# STM32F103C8T6.net
KiCad netlist of a schematic drawn in Altium Designer
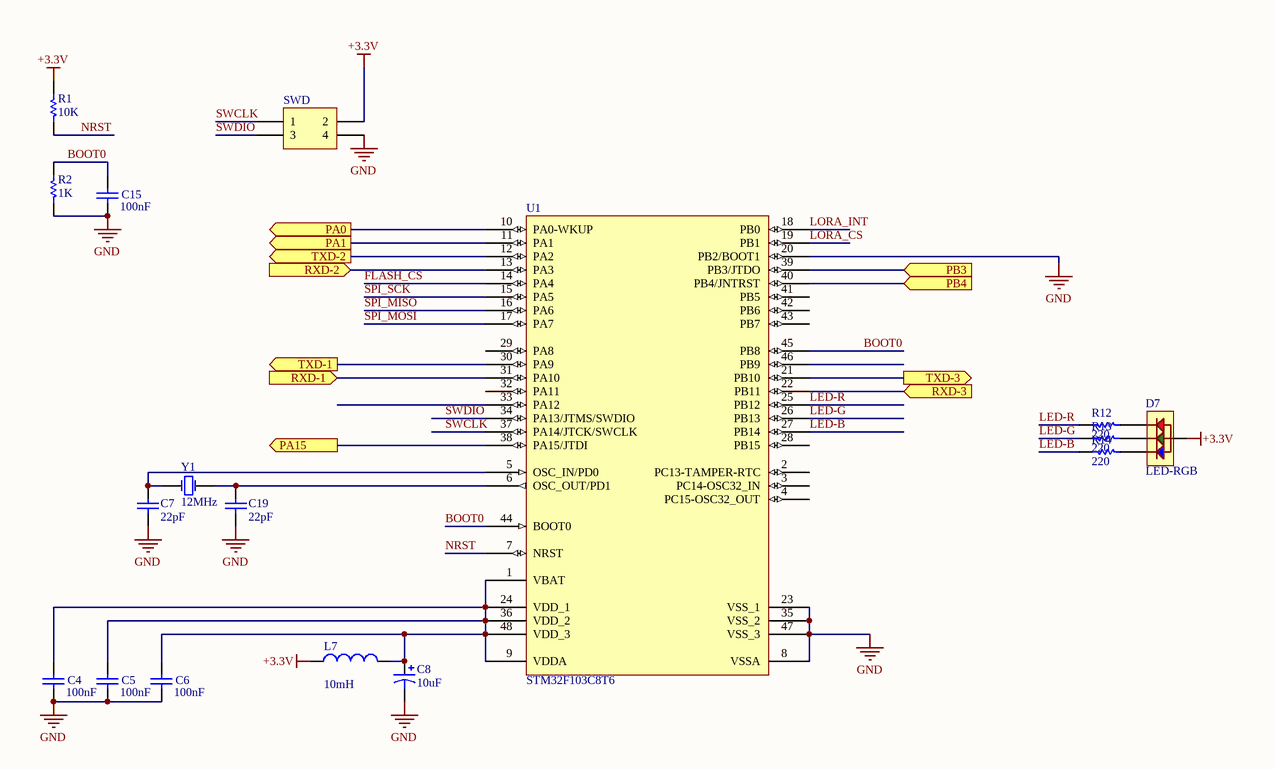
[diagram p0: STM32F103C8T6.SchDoc]

(export (version "E")
  (design (tool "Eeschema 10.0.6"))
  (components
    (comp (ref "C4")
      (value "100nF")
      (footprint "C603")
      (description "Capacitor")
      (fields (field (name "DESIGNER") "Parsa Malekpour"))
      (libsource (lib "UserPKG") (part "Cap"))
    )
    (comp (ref "C5")
      (value "100nF")
      (footprint "C603")
      (description "Capacitor")
      (fields (field (name "DESIGNER") "Parsa Malekpour"))
      (libsource (lib "UserPKG") (part "Cap"))
    )
    (comp (ref "C6")
      (value "100nF")
      (footprint "C603")
      (description "Capacitor")
      (fields (field (name "DESIGNER") "Parsa Malekpour"))
      (libsource (lib "UserPKG") (part "Cap"))
    )
    (comp (ref "C7")
      (value "22pF")
      (footprint "C603")
      (description "Capacitor")
      (fields (field (name "DESIGNER") "Parsa Malekpour"))
      (libsource (lib "UserPKG") (part "Cap"))
    )
    (comp (ref "C8")
      (value "10uF")
      (footprint "c805")
      (description "Polar Capacitor")
      (fields (field (name "VOLTAGE") "10V"))
      (libsource (lib "UserPKG") (part "CAP-POL"))
    )
    (comp (ref "C15")
      (value "100nF")
      (footprint "C603")
      (description "Capacitor")
      (fields (field (name "DESIGNER") "Parsa Malekpour"))
      (libsource (lib "UserPKG") (part "Cap"))
    )
    (comp (ref "C19")
      (value "22pF")
      (footprint "C603")
      (description "Capacitor")
      (fields (field (name "DESIGNER") "Parsa Malekpour"))
      (libsource (lib "UserPKG") (part "Cap"))
    )
    (comp (ref "D7")
      (value "LED-RGB")
      (footprint "LED-1210")
      (libsource (lib "ParsaLibrary") (part "LED-RGB-1210"))
    )
    (comp (ref "L7")
      (value "10mH")
      (footprint "R805")
      (description "Inductor")
      (fields (field (name "PUBLISHER") "Altium Limited"))
      (libsource (lib "Miscellaneous Devices") (part "Inductor"))
    )
    (comp (ref "R1")
      (value "10K")
      (footprint "R0603")
      (description "Resistor")
      (fields (field (name "DESIGNER") "Parsa Malekpour"))
      (libsource (lib "UserPKG") (part "Resistor"))
    )
    (comp (ref "R2")
      (value "1K")
      (footprint "R0603")
      (description "Resistor")
      (fields (field (name "DESIGNER") "Parsa Malekpour"))
      (libsource (lib "UserPKG") (part "Resistor"))
    )
    (comp (ref "R12")
      (value "220")
      (footprint "R0603")
      (description "Resistor")
      (fields (field (name "DESIGNER") "Parsa Malekpour"))
      (libsource (lib "UserPKG") (part "Resistor"))
    )
    (comp (ref "R13")
      (value "220")
      (footprint "R0603")
      (description "Resistor")
      (fields (field (name "DESIGNER") "Parsa Malekpour"))
      (libsource (lib "UserPKG") (part "Resistor"))
    )
    (comp (ref "R14")
      (value "220")
      (footprint "R0603")
      (description "Resistor")
      (fields (field (name "DESIGNER") "Parsa Malekpour"))
      (libsource (lib "UserPKG") (part "Resistor"))
    )
    (comp (ref "SWD")
      (value "MHDR2X2")
      (footprint "PHDR-2MM-2X2")
      (description "Header, 2-Pin, Dual row")
      (fields (field (name "PUBLISHER") "Altium Limited"))
      (libsource (lib "Miscellaneous Connectors") (part "MHDR2X2"))
    )
    (comp (ref "U1")
      (value "STM32F103C8T6")
      (footprint "LQFP-48")
      (description "STM32 ARM-based 32-bit MCU with 64 Kbytes Flash, 48-pin LQFP, Industrial Temperature")
      (fields (field (name "PUBLISHER") "Altium Limited"))
      (libsource (lib "ST Microcontroller 32-Bit STM32") (part "STM32F103C8T6"))
    )
    (comp (ref "Y1")
      (value "12MHz")
      (footprint "XTAL-SMD")
      (description "Crystal Oscillator")
      (fields (field (name "DESIGNER") "Parsa Malekpour") (field (name "EMAIL") "Malekpour.parsa@Gmail.com"))
      (libsource (lib "ParsaLibrary") (part "XTAL"))
    )
  )
  (nets
    (net (code "1") (name "+3.3V") (class "Default")
      (node (ref "D7") (pin "4") (pinfunction "COM_4") (pintype "passive"))
      (node (ref "L7") (pin "1") (pinfunction "1_1") (pintype "passive"))
      (node (ref "R1") (pin "2") (pinfunction "2_2") (pintype "passive"))
      (node (ref "SWD") (pin "2") (pinfunction "2_2") (pintype "passive"))
    )
    (net (code "2") (name "/BOOT0") (class "Default")
      (node (ref "C15") (pin "2") (pinfunction "2_2") (pintype "passive"))
      (node (ref "R2") (pin "2") (pinfunction "2_2") (pintype "passive"))
      (node (ref "U1") (pin "44") (pinfunction "BOOT0_44") (pintype "input"))
      (node (ref "U1") (pin "45") (pinfunction "PB8_45") (pintype "bidirectional"))
    )
    (net (code "3") (name "/FLASH_CS") (class "Default")
      (node (ref "U1") (pin "14") (pinfunction "PA4_14") (pintype "bidirectional"))
    )
    (net (code "4") (name "/LED-B") (class "Default")
      (node (ref "R14") (pin "2") (pinfunction "2_2") (pintype "passive"))
      (node (ref "U1") (pin "27") (pinfunction "PB14_27") (pintype "bidirectional"))
    )
    (net (code "5") (name "/LED-G") (class "Default")
      (node (ref "R13") (pin "2") (pinfunction "2_2") (pintype "passive"))
      (node (ref "U1") (pin "26") (pinfunction "PB13_26") (pintype "bidirectional"))
    )
    (net (code "6") (name "/LED-R") (class "Default")
      (node (ref "R12") (pin "2") (pinfunction "2_2") (pintype "passive"))
      (node (ref "U1") (pin "25") (pinfunction "PB12_25") (pintype "bidirectional"))
    )
    (net (code "7") (name "/LORA_CS") (class "Default")
      (node (ref "U1") (pin "19") (pinfunction "PB1_19") (pintype "bidirectional"))
    )
    (net (code "8") (name "/LORA_INT") (class "Default")
      (node (ref "U1") (pin "18") (pinfunction "PB0_18") (pintype "bidirectional"))
    )
    (net (code "9") (name "/NRST") (class "Default")
      (node (ref "R1") (pin "1") (pinfunction "1_1") (pintype "passive"))
      (node (ref "U1") (pin "7") (pinfunction "NRST_7") (pintype "bidirectional"))
    )
    (net (code "10") (name "/PA0") (class "Default")
      (node (ref "U1") (pin "10") (pinfunction "PA0-WKUP_10") (pintype "bidirectional"))
    )
    (net (code "11") (name "/PA1") (class "Default")
      (node (ref "U1") (pin "11") (pinfunction "PA1_11") (pintype "bidirectional"))
    )
    (net (code "12") (name "/PA15") (class "Default")
      (node (ref "U1") (pin "38") (pinfunction "PA15/JTDI_38") (pintype "bidirectional"))
    )
    (net (code "13") (name "/PB3") (class "Default")
      (node (ref "U1") (pin "39") (pinfunction "PB3/JTDO_39") (pintype "bidirectional"))
    )
    (net (code "14") (name "/PB4") (class "Default")
      (node (ref "U1") (pin "40") (pinfunction "PB4/JNTRST_40") (pintype "bidirectional"))
    )
    (net (code "15") (name "/RXD-1") (class "Default")
      (node (ref "U1") (pin "31") (pinfunction "PA10_31") (pintype "bidirectional"))
    )
    (net (code "16") (name "/RXD-2") (class "Default")
      (node (ref "U1") (pin "13") (pinfunction "PA3_13") (pintype "bidirectional"))
    )
    (net (code "17") (name "/RXD-3") (class "Default")
      (node (ref "U1") (pin "22") (pinfunction "PB11_22") (pintype "bidirectional"))
    )
    (net (code "18") (name "/SPI_MISO") (class "Default")
      (node (ref "U1") (pin "16") (pinfunction "PA6_16") (pintype "bidirectional"))
    )
    (net (code "19") (name "/SPI_MOSI") (class "Default")
      (node (ref "U1") (pin "17") (pinfunction "PA7_17") (pintype "bidirectional"))
    )
    (net (code "20") (name "/SPI_SCK") (class "Default")
      (node (ref "U1") (pin "15") (pinfunction "PA5_15") (pintype "bidirectional"))
    )
    (net (code "21") (name "/SWCLK") (class "Default")
      (node (ref "SWD") (pin "1") (pinfunction "1_1") (pintype "passive"))
      (node (ref "U1") (pin "37") (pinfunction "PA14/JTCK/SWCLK_37") (pintype "bidirectional"))
    )
    (net (code "22") (name "/SWDIO") (class "Default")
      (node (ref "SWD") (pin "3") (pinfunction "3_3") (pintype "passive"))
      (node (ref "U1") (pin "34") (pinfunction "PA13/JTMS/SWDIO_34") (pintype "bidirectional"))
    )
    (net (code "23") (name "/TXD-1") (class "Default")
      (node (ref "U1") (pin "30") (pinfunction "PA9_30") (pintype "bidirectional"))
    )
    (net (code "24") (name "/TXD-2") (class "Default")
      (node (ref "U1") (pin "12") (pinfunction "PA2_12") (pintype "bidirectional"))
    )
    (net (code "25") (name "/TXD-3") (class "Default")
      (node (ref "U1") (pin "21") (pinfunction "PB10_21") (pintype "bidirectional"))
    )
    (net (code "26") (name "GND") (class "Default")
      (node (ref "C15") (pin "1") (pinfunction "1_1") (pintype "passive"))
      (node (ref "C19") (pin "2") (pinfunction "2_2") (pintype "passive"))
      (node (ref "C4") (pin "1") (pinfunction "1_1") (pintype "passive"))
      (node (ref "C5") (pin "1") (pinfunction "1_1") (pintype "passive"))
      (node (ref "C6") (pin "1") (pinfunction "1_1") (pintype "passive"))
      (node (ref "C7") (pin "2") (pinfunction "2_2") (pintype "passive"))
      (node (ref "C8") (pin "2") (pinfunction "2_2") (pintype "passive"))
      (node (ref "R2") (pin "1") (pinfunction "1_1") (pintype "passive"))
      (node (ref "SWD") (pin "4") (pinfunction "4_4") (pintype "passive"))
      (node (ref "U1") (pin "20") (pinfunction "PB2/BOOT1_20") (pintype "bidirectional"))
      (node (ref "U1") (pin "23") (pinfunction "VSS_1_23") (pintype "power_in"))
      (node (ref "U1") (pin "35") (pinfunction "VSS_2_35") (pintype "power_in"))
      (node (ref "U1") (pin "47") (pinfunction "VSS_3_47") (pintype "power_in"))
      (node (ref "U1") (pin "8") (pinfunction "VSSA_8") (pintype "power_in"))
    )
    (net (code "27") (name "Net-(D7-B)") (class "Default")
      (node (ref "D7") (pin "1") (pinfunction "B_1") (pintype "passive"))
      (node (ref "R14") (pin "1") (pinfunction "1_1") (pintype "passive"))
    )
    (net (code "28") (name "Net-(D7-G)") (class "Default")
      (node (ref "D7") (pin "2") (pinfunction "G_2") (pintype "passive"))
      (node (ref "R13") (pin "1") (pinfunction "1_1") (pintype "passive"))
    )
    (net (code "29") (name "Net-(D7-R)") (class "Default")
      (node (ref "D7") (pin "3") (pinfunction "R_3") (pintype "passive"))
      (node (ref "R12") (pin "1") (pinfunction "1_1") (pintype "passive"))
    )
    (net (code "30") (name "Net-(U1-OSC_IN{slash}PD0)") (class "Default")
      (node (ref "C7") (pin "1") (pinfunction "1_1") (pintype "passive"))
      (node (ref "U1") (pin "5") (pinfunction "OSC_IN/PD0_5") (pintype "input"))
      (node (ref "Y1") (pin "1") (pinfunction "OSC1_1") (pintype "passive"))
    )
    (net (code "31") (name "Net-(U1-OSC_OUT{slash}PD1)") (class "Default")
      (node (ref "C19") (pin "1") (pinfunction "1_1") (pintype "passive"))
      (node (ref "U1") (pin "6") (pinfunction "OSC_OUT/PD1_6") (pintype "output"))
      (node (ref "Y1") (pin "2") (pinfunction "OSC2_2") (pintype "passive"))
    )
    (net (code "32") (name "Net-(U1-VBAT)") (class "Default")
      (node (ref "C4") (pin "2") (pinfunction "2_2") (pintype "passive"))
      (node (ref "C5") (pin "2") (pinfunction "2_2") (pintype "passive"))
      (node (ref "C6") (pin "2") (pinfunction "2_2") (pintype "passive"))
      (node (ref "C8") (pin "1") (pinfunction "1_1") (pintype "passive"))
      (node (ref "L7") (pin "2") (pinfunction "2_2") (pintype "passive"))
      (node (ref "U1") (pin "1") (pinfunction "VBAT_1") (pintype "power_in"))
      (node (ref "U1") (pin "24") (pinfunction "VDD_1_24") (pintype "power_in"))
      (node (ref "U1") (pin "36") (pinfunction "VDD_2_36") (pintype "power_in"))
      (node (ref "U1") (pin "48") (pinfunction "VDD_3_48") (pintype "power_in"))
      (node (ref "U1") (pin "9") (pinfunction "VDDA_9") (pintype "power_in"))
    )
    (net (code "33") (name "unconnected-(U1-PA8-Pad29)") (class "Default")
      (node (ref "U1") (pin "29") (pinfunction "PA8_29") (pintype "bidirectional"))
    )
    (net (code "34") (name "unconnected-(U1-PA11-Pad32)") (class "Default")
      (node (ref "U1") (pin "32") (pinfunction "PA11_32") (pintype "bidirectional"))
    )
    (net (code "35") (name "unconnected-(U1-PA12-Pad33)") (class "Default")
      (node (ref "U1") (pin "33") (pinfunction "PA12_33") (pintype "bidirectional"))
    )
    (net (code "36") (name "unconnected-(U1-PB5-Pad41)") (class "Default")
      (node (ref "U1") (pin "41") (pinfunction "PB5_41") (pintype "bidirectional"))
    )
    (net (code "37") (name "unconnected-(U1-PB6-Pad42)") (class "Default")
      (node (ref "U1") (pin "42") (pinfunction "PB6_42") (pintype "bidirectional"))
    )
    (net (code "38") (name "unconnected-(U1-PB7-Pad43)") (class "Default")
      (node (ref "U1") (pin "43") (pinfunction "PB7_43") (pintype "bidirectional"))
    )
    (net (code "39") (name "unconnected-(U1-PB9-Pad46)") (class "Default")
      (node (ref "U1") (pin "46") (pinfunction "PB9_46") (pintype "bidirectional"))
    )
    (net (code "40") (name "unconnected-(U1-PB15-Pad28)") (class "Default")
      (node (ref "U1") (pin "28") (pinfunction "PB15_28") (pintype "bidirectional"))
    )
    (net (code "41") (name "unconnected-(U1-PC13-TAMPER-RTC-Pad2)") (class "Default")
      (node (ref "U1") (pin "2") (pinfunction "PC13-TAMPER-RTC_2") (pintype "bidirectional"))
    )
    (net (code "42") (name "unconnected-(U1-PC14-OSC32_IN-Pad3)") (class "Default")
      (node (ref "U1") (pin "3") (pinfunction "PC14-OSC32_IN_3") (pintype "bidirectional"))
    )
    (net (code "43") (name "unconnected-(U1-PC15-OSC32_OUT-Pad4)") (class "Default")
      (node (ref "U1") (pin "4") (pinfunction "PC15-OSC32_OUT_4") (pintype "bidirectional"))
    )
  )
)
